# SCH_Endurance_drone_2.net
KiCad netlist of a schematic drawn in EasyEDA
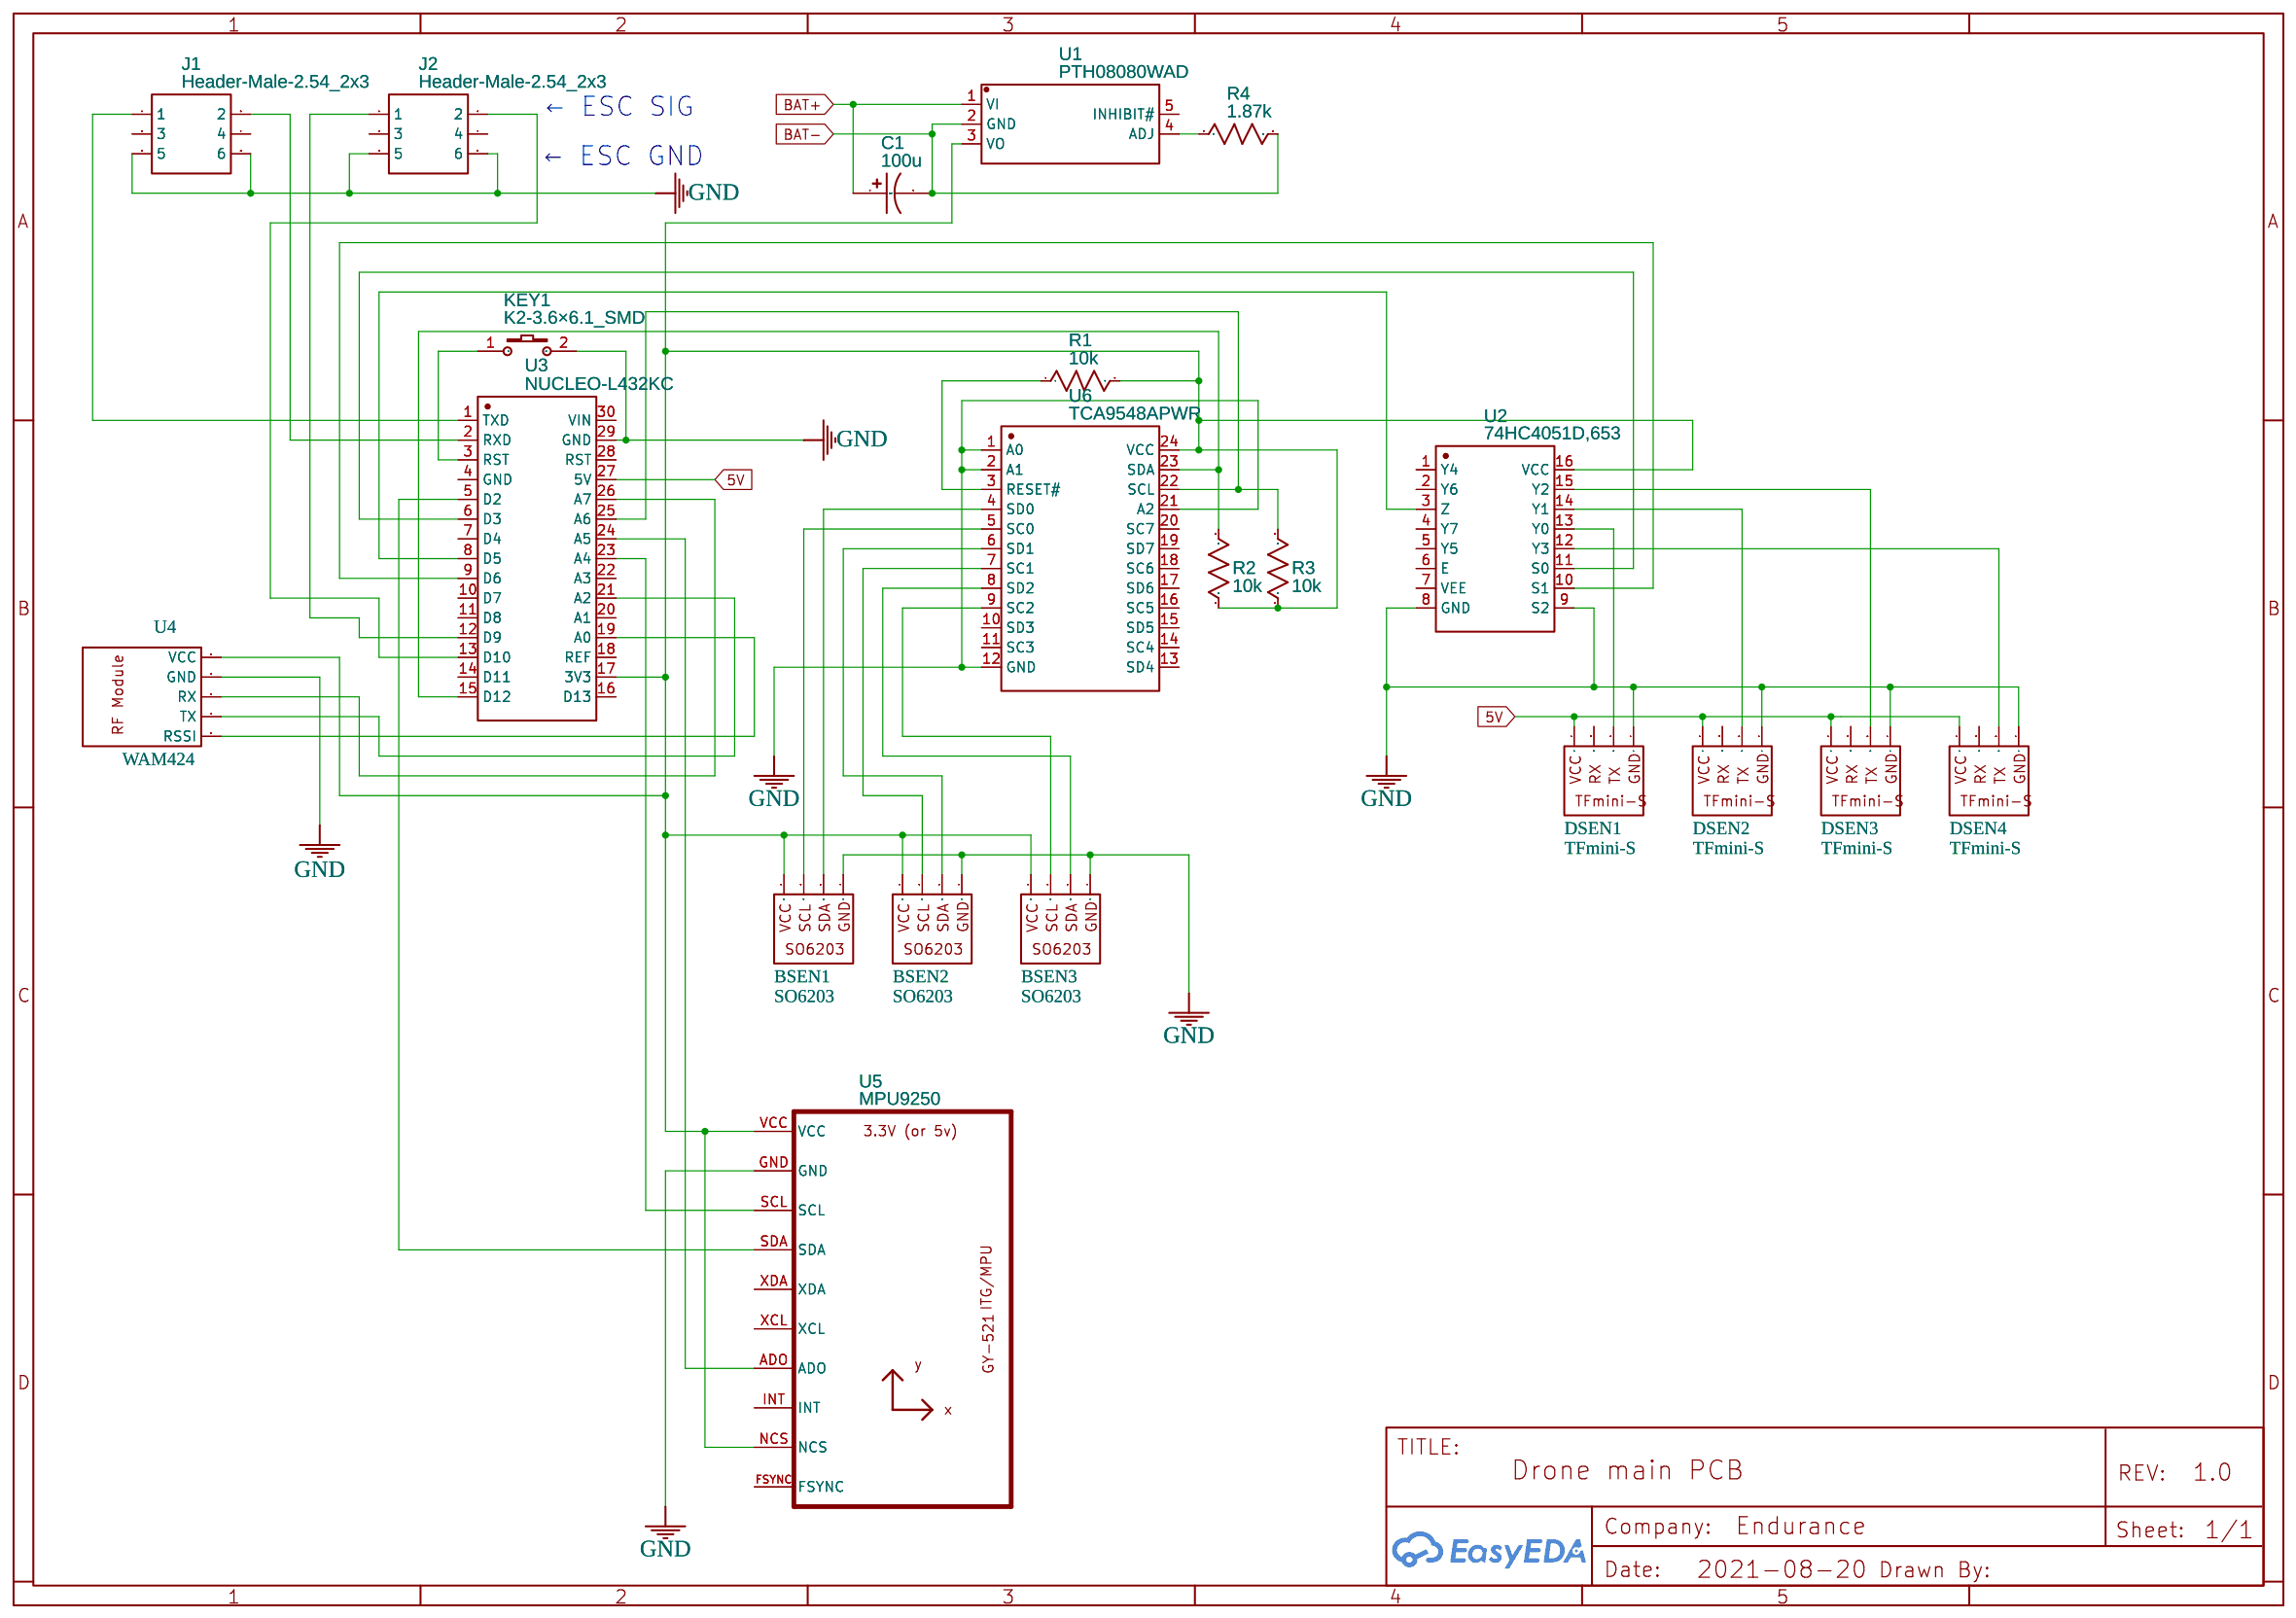
[diagram p0: schematic sheet]

(export (version "E")
  (design (tool "Eeschema 10.0.6"))
  (components
    (comp (ref "BSEN1") (value "SO6203") (libsource (lib "") (part "Unknown_405_-350")))
    (comp (ref "BSEN2") (value "SO6203") (libsource (lib "") (part "Unknown_465_-350")))
    (comp (ref "BSEN3") (value "SO6203") (libsource (lib "") (part "Unknown_530_-350")))
    (comp (ref "C1") (value "100u") (libsource (lib "") (part "C_Tan_SMD_A_US")))
    (comp (ref "DSEN1") (value "TFmini-S") (libsource (lib "") (part "Unknown_805_-425")))
    (comp (ref "DSEN2") (value "TFmini-S") (libsource (lib "") (part "Unknown_870_-425")))
    (comp (ref "DSEN3") (value "TFmini-S") (libsource (lib "") (part "Unknown_935_-425")))
    (comp (ref "DSEN4") (value "TFmini-S") (libsource (lib "") (part "Unknown_1000_-425")))
    (comp (ref "J1")
      (value "Header-Male-2.54_2x3")
      (fields (field (name "BOM_Supplier Part") "C65114"))
      (libsource (lib "") (part "Header-Male-2.54_2x3"))
    )
    (comp (ref "J2")
      (value "Header-Male-2.54_2x3")
      (fields (field (name "BOM_Supplier Part") "C65114"))
      (libsource (lib "") (part "Header-Male-2.54_2x3"))
    )
    (comp (ref "KEY1")
      (value "K2-3.6×6.1_SMD")
      (fields
        (field (name "BOM_Manufacturer Part") "K2-1107ST-A4SW-06")
        (field (name "BOM_Supplier Part") "C118141")
      )
      (libsource (lib "") (part "K2-3.6×6.1_SMD"))
    )
    (comp (ref "R1") (value "10k") (libsource (lib "") (part "R_0603_US_1")))
    (comp (ref "R2") (value "10k") (libsource (lib "") (part "R_0603_US")))
    (comp (ref "R3") (value "10k") (libsource (lib "") (part "R_0603_US")))
    (comp (ref "R4") (value "1.87k") (libsource (lib "") (part "R_0603_US_1")))
    (comp (ref "U1")
      (value "PTH08080WAD")
      (fields (field (name "BOM_Supplier Part") "C154927"))
      (libsource (lib "") (part "PTH08080WAD"))
    )
    (comp (ref "U2")
      (value "74HC4051D,653")
      (fields (field (name "BOM_Supplier Part") "C9386"))
      (libsource (lib "") (part "74HC4051D,653"))
    )
    (comp (ref "U3")
      (value "NUCLEO-L432KC")
      (fields (field (name "BOM_Supplier Part") "C94814"))
      (libsource (lib "") (part "NUCLEO-L432KC"))
    )
    (comp (ref "U4") (value "WAM424") (libsource (lib "") (part "Unknown_70_-460")))
    (comp (ref "U5") (value "MPU9250") (libsource (lib "") (part "MPU9250")))
    (comp (ref "U6")
      (value "TCA9548APWR")
      (fields (field (name "BOM_Supplier Part") "C130026"))
      (libsource (lib "") (part "TCA9548APWR"))
    )
  )
  (nets
    (net (code "1") (name "5V") (class "Default")
      (node (ref "DSEN1") (pin "1") (pinfunction "1_1") (pintype "unspecified"))
      (node (ref "DSEN2") (pin "1") (pinfunction "1_1") (pintype "unspecified"))
      (node (ref "DSEN3") (pin "1") (pinfunction "1_1") (pintype "unspecified"))
      (node (ref "DSEN4") (pin "1") (pinfunction "1_1") (pintype "unspecified"))
      (node (ref "U3") (pin "27") (pinfunction "5V_27") (pintype "unspecified"))
    )
    (net (code "2") (name "BAT+") (class "Default")
      (node (ref "C1") (pin "1") (pinfunction "1_1") (pintype "unspecified"))
      (node (ref "U1") (pin "1") (pinfunction "VI_1") (pintype "unspecified"))
    )
    (net (code "3") (name "BAT-") (class "Default")
      (node (ref "C1") (pin "2") (pinfunction "2_2") (pintype "unspecified"))
      (node (ref "R4") (pin "2") (pinfunction "2_2") (pintype "unspecified"))
      (node (ref "U1") (pin "2") (pinfunction "GND_2") (pintype "unspecified"))
    )
    (net (code "4") (name "GND") (class "Default")
      (node (ref "BSEN1") (pin "4") (pinfunction "4_4") (pintype "unspecified"))
      (node (ref "BSEN2") (pin "4") (pinfunction "4_4") (pintype "unspecified"))
      (node (ref "BSEN3") (pin "4") (pinfunction "4_4") (pintype "unspecified"))
      (node (ref "DSEN1") (pin "4") (pinfunction "4_4") (pintype "unspecified"))
      (node (ref "DSEN2") (pin "4") (pinfunction "4_4") (pintype "unspecified"))
      (node (ref "DSEN3") (pin "4") (pinfunction "4_4") (pintype "unspecified"))
      (node (ref "DSEN4") (pin "4") (pinfunction "4_4") (pintype "unspecified"))
      (node (ref "J1") (pin "5") (pinfunction "5_5") (pintype "input"))
      (node (ref "J1") (pin "6") (pinfunction "6_6") (pintype "input"))
      (node (ref "J2") (pin "5") (pinfunction "5_5") (pintype "input"))
      (node (ref "J2") (pin "6") (pinfunction "6_6") (pintype "input"))
      (node (ref "KEY1") (pin "2") (pinfunction "2_2") (pintype "unspecified"))
      (node (ref "U2") (pin "8") (pinfunction "GND_8") (pintype "unspecified"))
      (node (ref "U2") (pin "9") (pinfunction "S2_9") (pintype "unspecified"))
      (node (ref "U3") (pin "29") (pinfunction "GND_29") (pintype "unspecified"))
      (node (ref "U4") (pin "2") (pinfunction "GND_2") (pintype "unspecified"))
      (node (ref "U5") (pin "GND") (pinfunction "GND_GND") (pintype "bidirectional"))
      (node (ref "U6") (pin "1") (pinfunction "A0_1") (pintype "unspecified"))
      (node (ref "U6") (pin "12") (pinfunction "GND_12") (pintype "unspecified"))
      (node (ref "U6") (pin "2") (pinfunction "A1_2") (pintype "unspecified"))
      (node (ref "U6") (pin "21") (pinfunction "A2_21") (pintype "unspecified"))
    )
    (net (code "5") (name "Net-(KEY1-Pad1)") (class "Default")
      (node (ref "KEY1") (pin "1") (pinfunction "1_1") (pintype "unspecified"))
      (node (ref "U3") (pin "3") (pinfunction "RST_3") (pintype "unspecified"))
    )
    (net (code "6") (name "Net-(U1-ADJ)") (class "Default")
      (node (ref "R4") (pin "1") (pinfunction "1_1") (pintype "unspecified"))
      (node (ref "U1") (pin "4") (pinfunction "ADJ_4") (pintype "unspecified"))
    )
    (net (code "7") (name "Net-(U1-VO)") (class "Default")
      (node (ref "BSEN1") (pin "1") (pinfunction "1_1") (pintype "unspecified"))
      (node (ref "BSEN2") (pin "1") (pinfunction "1_1") (pintype "unspecified"))
      (node (ref "BSEN3") (pin "1") (pinfunction "1_1") (pintype "unspecified"))
      (node (ref "R1") (pin "2") (pinfunction "2_2") (pintype "unspecified"))
      (node (ref "R2") (pin "1") (pinfunction "1_1") (pintype "unspecified"))
      (node (ref "R3") (pin "1") (pinfunction "1_1") (pintype "unspecified"))
      (node (ref "U1") (pin "3") (pinfunction "VO_3") (pintype "unspecified"))
      (node (ref "U2") (pin "16") (pinfunction "VCC_16") (pintype "unspecified"))
      (node (ref "U3") (pin "17") (pinfunction "3V3_17") (pintype "unspecified"))
      (node (ref "U4") (pin "1") (pinfunction "VCC_1") (pintype "unspecified"))
      (node (ref "U5") (pin "NCS") (pinfunction "NCS_NCS") (pintype "bidirectional"))
      (node (ref "U5") (pin "VCC") (pinfunction "VCC_VCC") (pintype "bidirectional"))
      (node (ref "U6") (pin "24") (pinfunction "VCC_24") (pintype "unspecified"))
    )
    (net (code "8") (name "Net-(U2-S0)") (class "Default")
      (node (ref "U2") (pin "11") (pinfunction "S0_11") (pintype "unspecified"))
      (node (ref "U3") (pin "6") (pinfunction "D3_6") (pintype "unspecified"))
    )
    (net (code "9") (name "Net-(U2-S1)") (class "Default")
      (node (ref "U2") (pin "10") (pinfunction "S1_10") (pintype "unspecified"))
      (node (ref "U3") (pin "9") (pinfunction "D6_9") (pintype "unspecified"))
    )
    (net (code "10") (name "Net-(U2-Y0)") (class "Default")
      (node (ref "DSEN1") (pin "3") (pinfunction "3_3") (pintype "unspecified"))
      (node (ref "U2") (pin "13") (pinfunction "Y0_13") (pintype "unspecified"))
    )
    (net (code "11") (name "Net-(U2-Y1)") (class "Default")
      (node (ref "DSEN2") (pin "3") (pinfunction "3_3") (pintype "unspecified"))
      (node (ref "U2") (pin "14") (pinfunction "Y1_14") (pintype "unspecified"))
    )
    (net (code "12") (name "Net-(U2-Y2)") (class "Default")
      (node (ref "DSEN3") (pin "3") (pinfunction "3_3") (pintype "unspecified"))
      (node (ref "U2") (pin "15") (pinfunction "Y2_15") (pintype "unspecified"))
    )
    (net (code "13") (name "Net-(U2-Y3)") (class "Default")
      (node (ref "DSEN4") (pin "3") (pinfunction "3_3") (pintype "unspecified"))
      (node (ref "U2") (pin "12") (pinfunction "Y3_12") (pintype "unspecified"))
    )
    (net (code "14") (name "Net-(U2-Z)") (class "Default")
      (node (ref "U2") (pin "3") (pinfunction "Z_3") (pintype "unspecified"))
      (node (ref "U3") (pin "8") (pinfunction "D5_8") (pintype "unspecified"))
    )
    (net (code "15") (name "Net-(U3-A0)") (class "Default")
      (node (ref "U3") (pin "19") (pinfunction "A0_19") (pintype "unspecified"))
      (node (ref "U4") (pin "5") (pinfunction "RSSI_5") (pintype "unspecified"))
    )
    (net (code "16") (name "Net-(U3-A2)") (class "Default")
      (node (ref "U3") (pin "21") (pinfunction "A2_21") (pintype "unspecified"))
      (node (ref "U4") (pin "4") (pinfunction "TX_4") (pintype "unspecified"))
    )
    (net (code "17") (name "Net-(U3-A4)") (class "Default")
      (node (ref "U3") (pin "23") (pinfunction "A4_23") (pintype "unspecified"))
      (node (ref "U5") (pin "SCL") (pinfunction "SCL_SCL") (pintype "bidirectional"))
    )
    (net (code "18") (name "Net-(U3-A5)") (class "Default")
      (node (ref "U3") (pin "24") (pinfunction "A5_24") (pintype "unspecified"))
      (node (ref "U5") (pin "ADO") (pinfunction "ADO_ADO") (pintype "bidirectional"))
    )
    (net (code "19") (name "Net-(U3-A6)") (class "Default")
      (node (ref "R3") (pin "2") (pinfunction "2_2") (pintype "unspecified"))
      (node (ref "U3") (pin "25") (pinfunction "A6_25") (pintype "unspecified"))
      (node (ref "U6") (pin "22") (pinfunction "SCL_22") (pintype "unspecified"))
    )
    (net (code "20") (name "Net-(U3-A7)") (class "Default")
      (node (ref "U3") (pin "26") (pinfunction "A7_26") (pintype "unspecified"))
      (node (ref "U4") (pin "3") (pinfunction "RX_3") (pintype "unspecified"))
    )
    (net (code "21") (name "Net-(U3-D2)") (class "Default")
      (node (ref "U3") (pin "5") (pinfunction "D2_5") (pintype "unspecified"))
      (node (ref "U5") (pin "SDA") (pinfunction "SDA_SDA") (pintype "bidirectional"))
    )
    (net (code "22") (name "Net-(U3-D9)") (class "Default")
      (node (ref "J2") (pin "1") (pinfunction "1_1") (pintype "input"))
      (node (ref "U3") (pin "12") (pinfunction "D9_12") (pintype "unspecified"))
    )
    (net (code "23") (name "Net-(U3-D10)") (class "Default")
      (node (ref "J2") (pin "2") (pinfunction "2_2") (pintype "input"))
      (node (ref "U3") (pin "13") (pinfunction "D10_13") (pintype "unspecified"))
    )
    (net (code "24") (name "Net-(U3-D12)") (class "Default")
      (node (ref "R2") (pin "2") (pinfunction "2_2") (pintype "unspecified"))
      (node (ref "U3") (pin "15") (pinfunction "D12_15") (pintype "unspecified"))
      (node (ref "U6") (pin "23") (pinfunction "SDA_23") (pintype "unspecified"))
    )
    (net (code "25") (name "Net-(U3-RXD)") (class "Default")
      (node (ref "J1") (pin "2") (pinfunction "2_2") (pintype "input"))
      (node (ref "U3") (pin "2") (pinfunction "RXD_2") (pintype "unspecified"))
    )
    (net (code "26") (name "Net-(U3-TXD)") (class "Default")
      (node (ref "J1") (pin "1") (pinfunction "1_1") (pintype "input"))
      (node (ref "U3") (pin "1") (pinfunction "TXD_1") (pintype "unspecified"))
    )
    (net (code "27") (name "Net-(U6-RESET#)") (class "Default")
      (node (ref "R1") (pin "1") (pinfunction "1_1") (pintype "unspecified"))
      (node (ref "U6") (pin "3") (pinfunction "RESET#_3") (pintype "unspecified"))
    )
    (net (code "28") (name "Net-(U6-SC0)") (class "Default")
      (node (ref "BSEN1") (pin "2") (pinfunction "2_2") (pintype "unspecified"))
      (node (ref "U6") (pin "5") (pinfunction "SC0_5") (pintype "unspecified"))
    )
    (net (code "29") (name "Net-(U6-SC1)") (class "Default")
      (node (ref "BSEN2") (pin "2") (pinfunction "2_2") (pintype "unspecified"))
      (node (ref "U6") (pin "7") (pinfunction "SC1_7") (pintype "unspecified"))
    )
    (net (code "30") (name "Net-(U6-SC2)") (class "Default")
      (node (ref "BSEN3") (pin "2") (pinfunction "2_2") (pintype "unspecified"))
      (node (ref "U6") (pin "9") (pinfunction "SC2_9") (pintype "unspecified"))
    )
    (net (code "31") (name "Net-(U6-SD0)") (class "Default")
      (node (ref "BSEN1") (pin "3") (pinfunction "3_3") (pintype "unspecified"))
      (node (ref "U6") (pin "4") (pinfunction "SD0_4") (pintype "unspecified"))
    )
    (net (code "32") (name "Net-(U6-SD1)") (class "Default")
      (node (ref "BSEN2") (pin "3") (pinfunction "3_3") (pintype "unspecified"))
      (node (ref "U6") (pin "6") (pinfunction "SD1_6") (pintype "unspecified"))
    )
    (net (code "33") (name "Net-(U6-SD2)") (class "Default")
      (node (ref "BSEN3") (pin "3") (pinfunction "3_3") (pintype "unspecified"))
      (node (ref "U6") (pin "8") (pinfunction "SD2_8") (pintype "unspecified"))
    )
    (net (code "34") (name "unconnected-(DSEN1-Pad2)") (class "Default")
      (node (ref "DSEN1") (pin "2") (pinfunction "2_2") (pintype "unspecified"))
    )
    (net (code "35") (name "unconnected-(DSEN2-Pad2)") (class "Default")
      (node (ref "DSEN2") (pin "2") (pinfunction "2_2") (pintype "unspecified"))
    )
    (net (code "36") (name "unconnected-(DSEN3-Pad2)") (class "Default")
      (node (ref "DSEN3") (pin "2") (pinfunction "2_2") (pintype "unspecified"))
    )
    (net (code "37") (name "unconnected-(DSEN4-Pad2)") (class "Default")
      (node (ref "DSEN4") (pin "2") (pinfunction "2_2") (pintype "unspecified"))
    )
    (net (code "38") (name "unconnected-(J1-Pad3)") (class "Default")
      (node (ref "J1") (pin "3") (pinfunction "3_3") (pintype "input"))
    )
    (net (code "39") (name "unconnected-(J1-Pad4)") (class "Default")
      (node (ref "J1") (pin "4") (pinfunction "4_4") (pintype "input"))
    )
    (net (code "40") (name "unconnected-(J2-Pad3)") (class "Default")
      (node (ref "J2") (pin "3") (pinfunction "3_3") (pintype "input"))
    )
    (net (code "41") (name "unconnected-(J2-Pad4)") (class "Default")
      (node (ref "J2") (pin "4") (pinfunction "4_4") (pintype "input"))
    )
    (net (code "42") (name "unconnected-(U1-INHIBIT#-Pad5)") (class "Default")
      (node (ref "U1") (pin "5") (pinfunction "INHIBIT#_5") (pintype "unspecified"))
    )
    (net (code "43") (name "unconnected-(U2-E-Pad6)") (class "Default")
      (node (ref "U2") (pin "6") (pinfunction "E_6") (pintype "unspecified"))
    )
    (net (code "44") (name "unconnected-(U2-VEE-Pad7)") (class "Default")
      (node (ref "U2") (pin "7") (pinfunction "VEE_7") (pintype "unspecified"))
    )
    (net (code "45") (name "unconnected-(U2-Y4-Pad1)") (class "Default")
      (node (ref "U2") (pin "1") (pinfunction "Y4_1") (pintype "unspecified"))
    )
    (net (code "46") (name "unconnected-(U2-Y5-Pad5)") (class "Default")
      (node (ref "U2") (pin "5") (pinfunction "Y5_5") (pintype "unspecified"))
    )
    (net (code "47") (name "unconnected-(U2-Y6-Pad2)") (class "Default")
      (node (ref "U2") (pin "2") (pinfunction "Y6_2") (pintype "unspecified"))
    )
    (net (code "48") (name "unconnected-(U2-Y7-Pad4)") (class "Default")
      (node (ref "U2") (pin "4") (pinfunction "Y7_4") (pintype "unspecified"))
    )
    (net (code "49") (name "unconnected-(U3-A1-Pad20)") (class "Default")
      (node (ref "U3") (pin "20") (pinfunction "A1_20") (pintype "unspecified"))
    )
    (net (code "50") (name "unconnected-(U3-A3-Pad22)") (class "Default")
      (node (ref "U3") (pin "22") (pinfunction "A3_22") (pintype "unspecified"))
    )
    (net (code "51") (name "unconnected-(U3-D4-Pad7)") (class "Default")
      (node (ref "U3") (pin "7") (pinfunction "D4_7") (pintype "unspecified"))
    )
    (net (code "52") (name "unconnected-(U3-D7-Pad10)") (class "Default")
      (node (ref "U3") (pin "10") (pinfunction "D7_10") (pintype "unspecified"))
    )
    (net (code "53") (name "unconnected-(U3-D8-Pad11)") (class "Default")
      (node (ref "U3") (pin "11") (pinfunction "D8_11") (pintype "unspecified"))
    )
    (net (code "54") (name "unconnected-(U3-D11-Pad14)") (class "Default")
      (node (ref "U3") (pin "14") (pinfunction "D11_14") (pintype "unspecified"))
    )
    (net (code "55") (name "unconnected-(U3-D13-Pad16)") (class "Default")
      (node (ref "U3") (pin "16") (pinfunction "D13_16") (pintype "unspecified"))
    )
    (net (code "56") (name "unconnected-(U3-GND-Pad4)") (class "Default")
      (node (ref "U3") (pin "4") (pinfunction "GND_4") (pintype "unspecified"))
    )
    (net (code "57") (name "unconnected-(U3-REF-Pad18)") (class "Default")
      (node (ref "U3") (pin "18") (pinfunction "REF_18") (pintype "unspecified"))
    )
    (net (code "58") (name "unconnected-(U3-RST-Pad28)") (class "Default")
      (node (ref "U3") (pin "28") (pinfunction "RST_28") (pintype "unspecified"))
    )
    (net (code "59") (name "unconnected-(U3-VIN-Pad30)") (class "Default")
      (node (ref "U3") (pin "30") (pinfunction "VIN_30") (pintype "unspecified"))
    )
    (net (code "60") (name "unconnected-(U5-PadFSYNC)") (class "Default")
      (node (ref "U5") (pin "FSYNC") (pinfunction "FSYNC_FSYNC") (pintype "bidirectional"))
    )
    (net (code "61") (name "unconnected-(U5-PadINT)") (class "Default")
      (node (ref "U5") (pin "INT") (pinfunction "INT_INT") (pintype "bidirectional"))
    )
    (net (code "62") (name "unconnected-(U5-PadXCL)") (class "Default")
      (node (ref "U5") (pin "XCL") (pinfunction "XCL_XCL") (pintype "bidirectional"))
    )
    (net (code "63") (name "unconnected-(U5-PadXDA)") (class "Default")
      (node (ref "U5") (pin "XDA") (pinfunction "XDA_XDA") (pintype "bidirectional"))
    )
    (net (code "64") (name "unconnected-(U6-SC3-Pad11)") (class "Default")
      (node (ref "U6") (pin "11") (pinfunction "SC3_11") (pintype "unspecified"))
    )
    (net (code "65") (name "unconnected-(U6-SC4-Pad14)") (class "Default")
      (node (ref "U6") (pin "14") (pinfunction "SC4_14") (pintype "unspecified"))
    )
    (net (code "66") (name "unconnected-(U6-SC5-Pad16)") (class "Default")
      (node (ref "U6") (pin "16") (pinfunction "SC5_16") (pintype "unspecified"))
    )
    (net (code "67") (name "unconnected-(U6-SC6-Pad18)") (class "Default")
      (node (ref "U6") (pin "18") (pinfunction "SC6_18") (pintype "unspecified"))
    )
    (net (code "68") (name "unconnected-(U6-SC7-Pad20)") (class "Default")
      (node (ref "U6") (pin "20") (pinfunction "SC7_20") (pintype "unspecified"))
    )
    (net (code "69") (name "unconnected-(U6-SD3-Pad10)") (class "Default")
      (node (ref "U6") (pin "10") (pinfunction "SD3_10") (pintype "unspecified"))
    )
    (net (code "70") (name "unconnected-(U6-SD4-Pad13)") (class "Default")
      (node (ref "U6") (pin "13") (pinfunction "SD4_13") (pintype "unspecified"))
    )
    (net (code "71") (name "unconnected-(U6-SD5-Pad15)") (class "Default")
      (node (ref "U6") (pin "15") (pinfunction "SD5_15") (pintype "unspecified"))
    )
    (net (code "72") (name "unconnected-(U6-SD6-Pad17)") (class "Default")
      (node (ref "U6") (pin "17") (pinfunction "SD6_17") (pintype "unspecified"))
    )
    (net (code "73") (name "unconnected-(U6-SD7-Pad19)") (class "Default")
      (node (ref "U6") (pin "19") (pinfunction "SD7_19") (pintype "unspecified"))
    )
  )
)
